# Battery_charging_module.net
KiCad netlist of a schematic drawn in Altium Designer
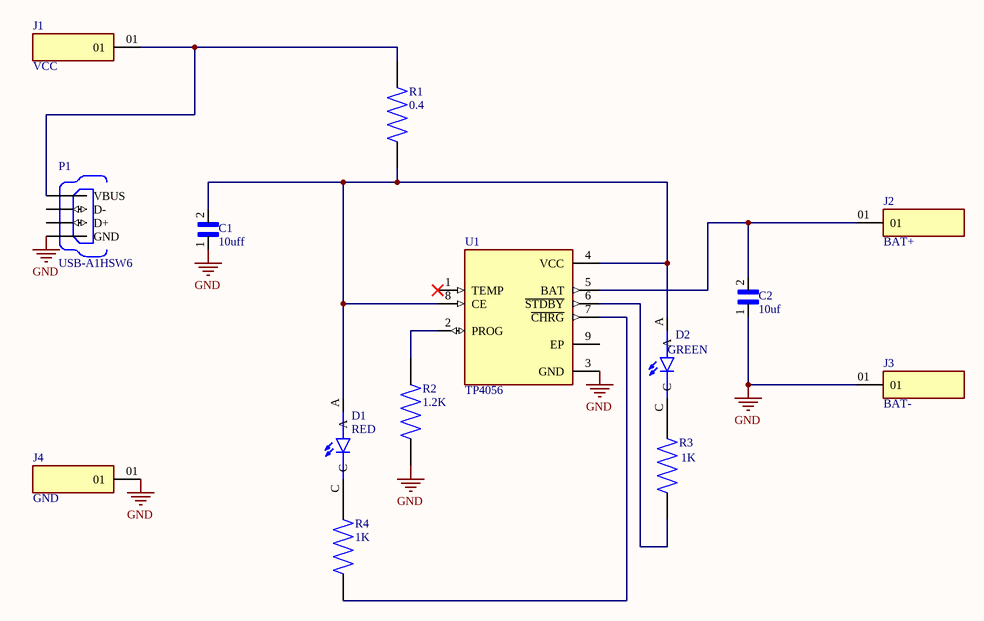
[diagram p0: Battery charging module.SchDoc]

(export (version "E")
  (design (tool "Eeschema 10.0.6"))
  (components
    (comp (ref "C1")
      (value "10uff")
      (footprint "CAPC2012X145N")
      (fields (field (name "MP") "GRM21BC81E106ME11L"))
      (libsource (lib "GRM21BC81E106ME11L") (part "GRM21BC81E106ME11L"))
    )
    (comp (ref "C2")
      (value "10uf")
      (footprint "CAPC2012X145N")
      (fields (field (name "MP") "GRM21BC81E106ME11L"))
      (libsource (lib "GRM21BC81E106ME11L") (part "GRM21BC81E106ME11L"))
    )
    (comp (ref "D1")
      (value "RED")
      (footprint "LEDC3216X110")
      (description "Red 631nm LED Indication - Discrete 2V 1206 _3216 Metric_")
      (fields (field (name "MF") "Lite-On Inc.") (field (name "DIGI-KEY_PART_NUMBER") "160-1457-1-ND"))
      (libsource (lib "SnapEDAsch") (part "LTST-C230KRKT"))
    )
    (comp (ref "D2")
      (value "GREEN")
      (footprint "LEDC3216X110")
      (description "Red 631nm LED Indication - Discrete 2V 1206 _3216 Metric_")
      (fields (field (name "MF") "Lite-On Inc.") (field (name "DIGI-KEY_PART_NUMBER") "160-1457-1-ND"))
      (libsource (lib "SnapEDAsch") (part "LTST-C230KRKT"))
    )
    (comp (ref "J1")
      (value "VCC")
      (footprint "SAMTEC_TMS-101-21-G-S")
      (fields (field (name "MP") "TMS-101-21-G-S"))
      (libsource (lib "TMS-101-21-G-S") (part "TMS-101-21-G-S"))
    )
    (comp (ref "J2")
      (value "BAT+")
      (footprint "SAMTEC_TMS-101-21-G-S")
      (fields (field (name "MP") "TMS-101-21-G-S"))
      (libsource (lib "") (part "TMS-101-21-G-S_1"))
    )
    (comp (ref "J3")
      (value "BAT-")
      (footprint "SAMTEC_TMS-101-21-G-S")
      (fields (field (name "MP") "TMS-101-21-G-S"))
      (libsource (lib "") (part "TMS-101-21-G-S_1"))
    )
    (comp (ref "J4")
      (value "GND")
      (footprint "SAMTEC_TMS-101-21-G-S")
      (fields (field (name "MP") "TMS-101-21-G-S"))
      (libsource (lib "TMS-101-21-G-S") (part "TMS-101-21-G-S"))
    )
    (comp (ref "P1")
      (value "USB-A1HSW6")
      (footprint "OST_USB-A1HSW6")
      (description "USB - A Receptacle Connector 4 Position Through Hole, Right Angle")
      (libsource (lib "USB-A1HSW6") (part "USB-A1HSW6"))
    )
    (comp (ref "R1")
      (value "0.4")
      (footprint "RESC5025X65N")
      (description "RES SMD 400 MOHM 5% 3/4W 2010")
      (fields (field (name "MP") "RL2010JK-070R4L"))
      (libsource (lib "RL2010JK-070R4L") (part "RL2010JK-070R4L"))
    )
    (comp (ref "R2")
      (value "1.2K")
      (footprint "RES_ERJP03D1201V")
      (fields (field (name "MP") "ERJP03D1201V"))
      (libsource (lib "ERJP03D1201V") (part "ERJP03D1201V"))
    )
    (comp (ref "R3")
      (value "1K")
      (footprint "RESC2012X65N")
      (description "RESISTOR, THIN FILM, 1K, 0.1%, 0805")
      (fields (field (name "MF") "TE Connectivity") (field (name "MP") "RN73C2A1K0BTG"))
      (libsource (lib "SnapEDAsch") (part "RN73C2A1K0BTG"))
    )
    (comp (ref "R4")
      (value "1K")
      (footprint "RESC2012X65N")
      (description "RESISTOR, THIN FILM, 1K, 0.1%, 0805")
      (fields (field (name "MF") "TE Connectivity") (field (name "MP") "RN73C2A1K0BTG"))
      (libsource (lib "SnapEDAsch") (part "RN73C2A1K0BTG"))
    )
    (comp (ref "U1")
      (value "TP4056")
      (footprint "SOP127P600X175-9N")
      (description "Complete single cell Li-Ion battery with a constant current / constant voltage linear charger")
      (libsource (lib "TP4056") (part "TP4056"))
    )
  )
  (nets
    (net (code "1") (name "GND") (class "Default")
      (node (ref "C1") (pin "1") (pinfunction "1_1") (pintype "passive"))
      (node (ref "C2") (pin "1") (pinfunction "1_1") (pintype "passive"))
      (node (ref "J3") (pin "01") (pinfunction "01_01") (pintype "passive"))
      (node (ref "J4") (pin "01") (pinfunction "01_01") (pintype "passive"))
      (node (ref "P1") (pin "4") (pinfunction "GND_4") (pintype "power_in"))
      (node (ref "R2") (pin "1") (pinfunction "1_1") (pintype "passive"))
      (node (ref "U1") (pin "3") (pinfunction "GND_3") (pintype "power_in"))
    )
    (net (code "2") (name "Net-(D1-PadC)") (class "Default")
      (node (ref "D1") (pin "C") (pinfunction "C_C") (pintype "passive"))
      (node (ref "R4") (pin "2") (pinfunction "2_2") (pintype "passive"))
    )
    (net (code "3") (name "Net-(D2-PadC)") (class "Default")
      (node (ref "D2") (pin "C") (pinfunction "C_C") (pintype "passive"))
      (node (ref "R3") (pin "2") (pinfunction "2_2") (pintype "passive"))
    )
    (net (code "4") (name "Net-(P1-VBUS)") (class "Default")
      (node (ref "J1") (pin "01") (pinfunction "01_01") (pintype "passive"))
      (node (ref "P1") (pin "1") (pinfunction "VBUS_1") (pintype "power_in"))
      (node (ref "R1") (pin "2") (pinfunction "2_2") (pintype "passive"))
    )
    (net (code "5") (name "Net-(U1-BAT)") (class "Default")
      (node (ref "C2") (pin "2") (pinfunction "2_2") (pintype "passive"))
      (node (ref "J2") (pin "01") (pinfunction "01_01") (pintype "passive"))
      (node (ref "U1") (pin "5") (pinfunction "BAT_5") (pintype "output"))
    )
    (net (code "6") (name "Net-(U1-CE)") (class "Default")
      (node (ref "C1") (pin "2") (pinfunction "2_2") (pintype "passive"))
      (node (ref "D1") (pin "A") (pinfunction "A_A") (pintype "passive"))
      (node (ref "D2") (pin "A") (pinfunction "A_A") (pintype "passive"))
      (node (ref "R1") (pin "1") (pinfunction "1_1") (pintype "passive"))
      (node (ref "U1") (pin "4") (pinfunction "VCC_4") (pintype "power_in"))
      (node (ref "U1") (pin "8") (pinfunction "CE_8") (pintype "input"))
    )
    (net (code "7") (name "Net-(U1-PROG)") (class "Default")
      (node (ref "R2") (pin "2") (pinfunction "2_2") (pintype "passive"))
      (node (ref "U1") (pin "2") (pinfunction "PROG_2") (pintype "bidirectional"))
    )
    (net (code "8") (name "Net-(U1-~{CHRG})") (class "Default")
      (node (ref "R4") (pin "1") (pinfunction "1_1") (pintype "passive"))
      (node (ref "U1") (pin "7") (pinfunction "~{CHRG}_7") (pintype "output"))
    )
    (net (code "9") (name "Net-(U1-~{STDBY})") (class "Default")
      (node (ref "R3") (pin "1") (pinfunction "1_1") (pintype "passive"))
      (node (ref "U1") (pin "6") (pinfunction "~{STDBY}_6") (pintype "output"))
    )
    (net (code "10") (name "unconnected-(P1-D+-Pad3)") (class "Default")
      (node (ref "P1") (pin "3") (pinfunction "D+_3") (pintype "bidirectional"))
    )
    (net (code "11") (name "unconnected-(P1-D--Pad2)") (class "Default")
      (node (ref "P1") (pin "2") (pinfunction "D-_2") (pintype "bidirectional"))
    )
    (net (code "12") (name "unconnected-(U1-EP-Pad9)") (class "Default")
      (node (ref "U1") (pin "9") (pinfunction "EP_9") (pintype "passive"))
    )
    (net (code "13") (name "unconnected-(U1-TEMP-Pad1)") (class "Default")
      (node (ref "U1") (pin "1") (pinfunction "TEMP_1") (pintype "input+no_connect"))
    )
  )
)
